# BB8_Flywheel_Motors.net
KiCad netlist of a schematic drawn in Altium Designer
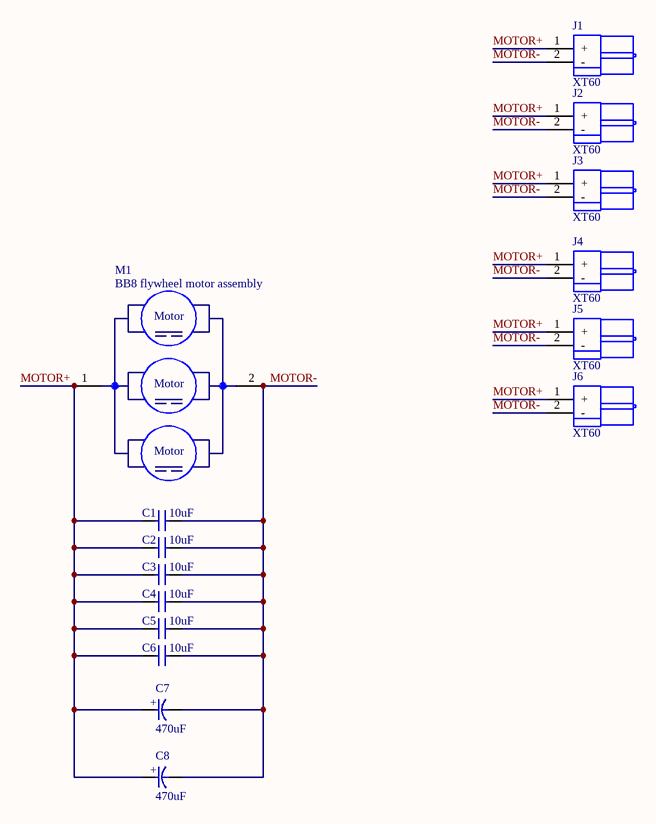
[diagram p0: BB8_Flywheel_Motors.SchDoc]

(export (version "E")
  (design (tool "Eeschema 10.0.6"))
  (components
    (comp (ref "C1")
      (value "10uF")
      (footprint "1210_Capacitor")
      (description "CAP CER 10UF 50V 10% X5R 1210")
      (fields
        (field (name "MANUFACTURER") "Taiyo Yuden")
        (field (name "Comment") "C_1210_10uF")
        (field (name "SVP CREATOR") "Matt Rogge")
      )
      (libsource (lib "capacitor") (part "C_1210_10uF"))
    )
    (comp (ref "C2")
      (value "10uF")
      (footprint "1210_Capacitor")
      (description "CAP CER 10UF 50V 10% X5R 1210")
      (fields
        (field (name "MANUFACTURER") "Taiyo Yuden")
        (field (name "Comment") "C_1210_10uF")
        (field (name "SVP CREATOR") "Matt Rogge")
      )
      (libsource (lib "capacitor") (part "C_1210_10uF"))
    )
    (comp (ref "C3")
      (value "10uF")
      (footprint "1210_Capacitor")
      (description "CAP CER 10UF 50V 10% X5R 1210")
      (fields
        (field (name "MANUFACTURER") "Taiyo Yuden")
        (field (name "Comment") "C_1210_10uF")
        (field (name "SVP CREATOR") "Matt Rogge")
      )
      (libsource (lib "capacitor") (part "C_1210_10uF"))
    )
    (comp (ref "C4")
      (value "10uF")
      (footprint "1210_Capacitor")
      (description "CAP CER 10UF 50V 10% X5R 1210")
      (fields
        (field (name "MANUFACTURER") "Taiyo Yuden")
        (field (name "Comment") "C_1210_10uF")
        (field (name "SVP CREATOR") "Matt Rogge")
      )
      (libsource (lib "capacitor") (part "C_1210_10uF"))
    )
    (comp (ref "C5")
      (value "10uF")
      (footprint "1210_Capacitor")
      (description "CAP CER 10UF 50V 10% X5R 1210")
      (fields
        (field (name "MANUFACTURER") "Taiyo Yuden")
        (field (name "Comment") "C_1210_10uF")
        (field (name "SVP CREATOR") "Matt Rogge")
      )
      (libsource (lib "capacitor") (part "C_1210_10uF"))
    )
    (comp (ref "C6")
      (value "10uF")
      (footprint "1210_Capacitor")
      (description "CAP CER 10UF 50V 10% X5R 1210")
      (fields
        (field (name "MANUFACTURER") "Taiyo Yuden")
        (field (name "Comment") "C_1210_10uF")
        (field (name "SVP CREATOR") "Matt Rogge")
      )
      (libsource (lib "capacitor") (part "C_1210_10uF"))
    )
    (comp (ref "C7")
      (value "470uF")
      (footprint "CAP_RADIAL_10x21.5mm_THRU")
      (description "470µF 50V Aluminum Capacitors Radial, Can 1000 Hrs @ 105°C")
      (fields (field (name "Comment") "EKMG500ETD471MJ20S"))
      (libsource (lib "capacitor") (part "C_EKMG500ETD471MJ20S"))
    )
    (comp (ref "C8")
      (value "470uF")
      (footprint "CAP_RADIAL_10x21.5mm_THRU")
      (description "470µF 50V Aluminum Capacitors Radial, Can 1000 Hrs @ 105°C")
      (fields (field (name "Comment") "EKMG500ETD471MJ20S"))
      (libsource (lib "capacitor") (part "C_EKMG500ETD471MJ20S"))
    )
    (comp (ref "J1")
      (value "XT60")
      (footprint "J_XT60_SMD_RA_Male")
      (description "60 Amp XT60 Connector")
      (libsource (lib "connector") (part "J_XT60"))
    )
    (comp (ref "J2")
      (value "XT60")
      (footprint "J_XT60_SMD_RA_Male")
      (description "60 Amp XT60 Connector")
      (libsource (lib "connector") (part "J_XT60"))
    )
    (comp (ref "J3")
      (value "XT60")
      (footprint "J_XT60_SMD_RA_Male")
      (description "60 Amp XT60 Connector")
      (libsource (lib "connector") (part "J_XT60"))
    )
    (comp (ref "J4")
      (value "XT60")
      (footprint "J_XT60_SMD_RA_Male")
      (description "60 Amp XT60 Connector")
      (libsource (lib "connector") (part "J_XT60"))
    )
    (comp (ref "J5")
      (value "XT60")
      (footprint "J_XT60_SMD_RA_Male")
      (description "60 Amp XT60 Connector")
      (libsource (lib "connector") (part "J_XT60"))
    )
    (comp (ref "J6")
      (value "XT60")
      (footprint "J_XT60_SMD_RA_Male")
      (description "60 Amp XT60 Connector")
      (libsource (lib "connector") (part "J_XT60"))
    )
    (comp (ref "M1")
      (value "BB8 flywheel motor assembly")
      (footprint "BB8_Flywheel_Motors_DC_36mm")
      (libsource (lib "misc") (part "BB8_Flywheel_Motors"))
    )
  )
  (nets
    (net (code "1") (name "/MOTOR+") (class "Default")
      (node (ref "C1") (pin "2") (pinfunction "2_2") (pintype "passive"))
      (node (ref "C2") (pin "2") (pinfunction "2_2") (pintype "passive"))
      (node (ref "C3") (pin "2") (pinfunction "2_2") (pintype "passive"))
      (node (ref "C4") (pin "2") (pinfunction "2_2") (pintype "passive"))
      (node (ref "C5") (pin "2") (pinfunction "2_2") (pintype "passive"))
      (node (ref "C6") (pin "2") (pinfunction "2_2") (pintype "passive"))
      (node (ref "C7") (pin "1") (pinfunction "1_1") (pintype "passive"))
      (node (ref "C8") (pin "1") (pinfunction "1_1") (pintype "passive"))
      (node (ref "J1") (pin "1") (pinfunction "+_1") (pintype "passive"))
      (node (ref "J2") (pin "1") (pinfunction "+_1") (pintype "passive"))
      (node (ref "J3") (pin "1") (pinfunction "+_1") (pintype "passive"))
      (node (ref "J4") (pin "1") (pinfunction "+_1") (pintype "passive"))
      (node (ref "J5") (pin "1") (pinfunction "+_1") (pintype "passive"))
      (node (ref "J6") (pin "1") (pinfunction "+_1") (pintype "passive"))
      (node (ref "M1") (pin "1") (pinfunction "1_1") (pintype "passive"))
    )
    (net (code "2") (name "/MOTOR-") (class "Default")
      (node (ref "C1") (pin "1") (pinfunction "1_1") (pintype "passive"))
      (node (ref "C2") (pin "1") (pinfunction "1_1") (pintype "passive"))
      (node (ref "C3") (pin "1") (pinfunction "1_1") (pintype "passive"))
      (node (ref "C4") (pin "1") (pinfunction "1_1") (pintype "passive"))
      (node (ref "C5") (pin "1") (pinfunction "1_1") (pintype "passive"))
      (node (ref "C6") (pin "1") (pinfunction "1_1") (pintype "passive"))
      (node (ref "C7") (pin "2") (pinfunction "2_2") (pintype "passive"))
      (node (ref "C8") (pin "2") (pinfunction "2_2") (pintype "passive"))
      (node (ref "J1") (pin "2") (pinfunction "-_2") (pintype "passive"))
      (node (ref "J2") (pin "2") (pinfunction "-_2") (pintype "passive"))
      (node (ref "J3") (pin "2") (pinfunction "-_2") (pintype "passive"))
      (node (ref "J4") (pin "2") (pinfunction "-_2") (pintype "passive"))
      (node (ref "J5") (pin "2") (pinfunction "-_2") (pintype "passive"))
      (node (ref "J6") (pin "2") (pinfunction "-_2") (pintype "passive"))
      (node (ref "M1") (pin "2") (pinfunction "2_2") (pintype "passive"))
    )
  )
)
